# LPC1768.net
KiCad netlist of a schematic drawn in Altium Designer
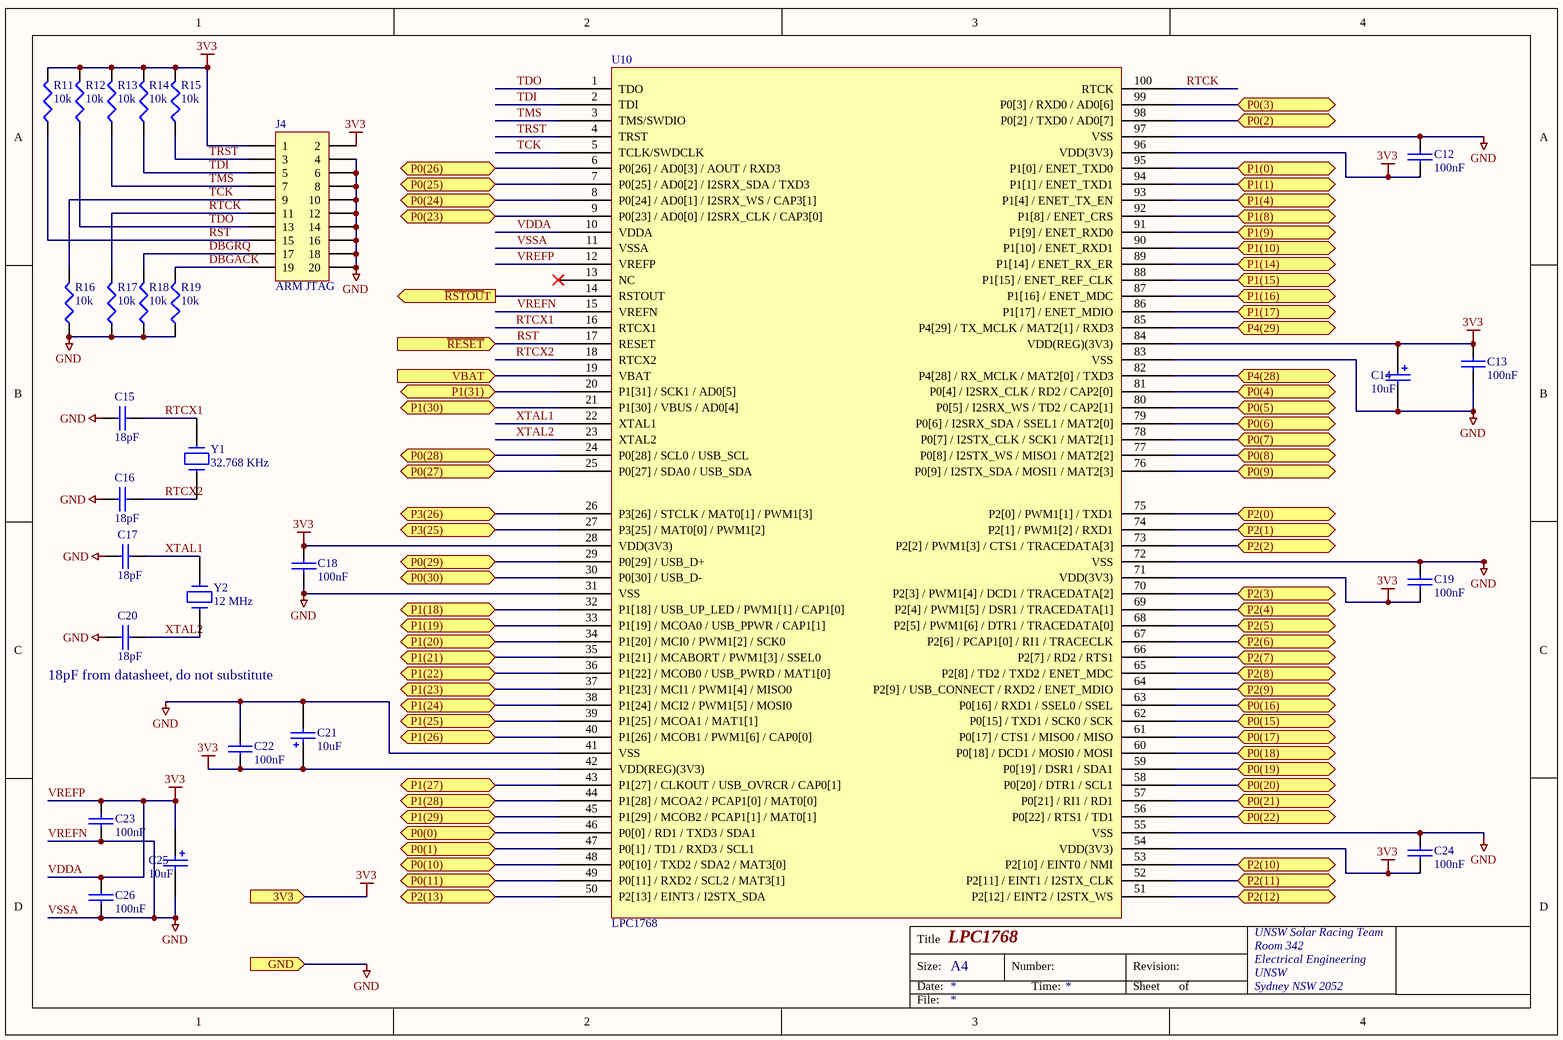
[diagram p0: LPC1768.SchDoc]

(export (version "E")
  (design (tool "Eeschema 10.0.6"))
  (components
    (comp (ref "C12")
      (value "100nF")
      (footprint "0603")
      (description "Capacitor")
      (libsource (lib "RCLDQ") (part "CAP"))
    )
    (comp (ref "C13")
      (value "100nF")
      (footprint "0603")
      (description "Capacitor")
      (libsource (lib "RCLDQ") (part "CAP"))
    )
    (comp (ref "C14")
      (value "10uF")
      (footprint "MCCT-CASEA")
      (description "Polarized Capacitor (Surface Mount)")
      (libsource (lib "RCLDQ") (part "CAP POL3"))
    )
    (comp (ref "C15")
      (value "18pF")
      (footprint "0603")
      (description "Capacitor")
      (libsource (lib "*") (part "CAP"))
    )
    (comp (ref "C16")
      (value "18pF")
      (footprint "0603")
      (description "Capacitor")
      (libsource (lib "*") (part "CAP"))
    )
    (comp (ref "C17")
      (value "18pF")
      (footprint "0603")
      (description "Capacitor")
      (libsource (lib "*") (part "CAP"))
    )
    (comp (ref "C18")
      (value "100nF")
      (footprint "0603")
      (description "Capacitor")
      (libsource (lib "RCLDQ") (part "CAP"))
    )
    (comp (ref "C19")
      (value "100nF")
      (footprint "0603")
      (description "Capacitor")
      (libsource (lib "RCLDQ") (part "CAP"))
    )
    (comp (ref "C20")
      (value "18pF")
      (footprint "0603")
      (description "Capacitor")
      (libsource (lib "*") (part "CAP"))
    )
    (comp (ref "C21")
      (value "10uF")
      (footprint "MCCT-CASEA")
      (description "Polarized Capacitor (Surface Mount)")
      (libsource (lib "RCLDQ") (part "CAP POL3"))
    )
    (comp (ref "C22")
      (value "100nF")
      (footprint "0603")
      (description "Capacitor")
      (libsource (lib "RCLDQ") (part "CAP"))
    )
    (comp (ref "C23")
      (value "100nF")
      (footprint "0603")
      (description "Capacitor")
      (libsource (lib "RCLDQ") (part "CAP"))
    )
    (comp (ref "C24")
      (value "100nF")
      (footprint "0603")
      (description "Capacitor")
      (libsource (lib "RCLDQ") (part "CAP"))
    )
    (comp (ref "C25")
      (value "10uF")
      (footprint "MCCT-CASEA")
      (description "Polarized Capacitor (Surface Mount)")
      (libsource (lib "RCLDQ") (part "CAP POL3"))
    )
    (comp (ref "C26")
      (value "100nF")
      (footprint "0603")
      (description "Capacitor")
      (libsource (lib "RCLDQ") (part "CAP"))
    )
    (comp (ref "J4")
      (value "ARM JTAG")
      (footprint "HDR2X10")
      (description "Header, 10-Pin, Dual row")
      (libsource (lib "Miscellaneous Connectors") (part "Header 10X2"))
    )
    (comp (ref "R11")
      (value "10k")
      (footprint "0603")
      (description "Resistor")
      (libsource (lib "RCLDQ") (part "RES1"))
    )
    (comp (ref "R12")
      (value "10k")
      (footprint "0603")
      (description "Resistor")
      (libsource (lib "RCLDQ") (part "RES1"))
    )
    (comp (ref "R13")
      (value "10k")
      (footprint "0603")
      (description "Resistor")
      (libsource (lib "RCLDQ") (part "RES1"))
    )
    (comp (ref "R14")
      (value "10k")
      (footprint "0603")
      (description "Resistor")
      (libsource (lib "RCLDQ") (part "RES1"))
    )
    (comp (ref "R15")
      (value "10k")
      (footprint "0603")
      (description "Resistor")
      (libsource (lib "RCLDQ") (part "RES1"))
    )
    (comp (ref "R16")
      (value "10k")
      (footprint "0603")
      (description "Resistor")
      (libsource (lib "RCLDQ") (part "RES1"))
    )
    (comp (ref "R17")
      (value "10k")
      (footprint "0603")
      (description "Resistor")
      (libsource (lib "RCLDQ") (part "RES1"))
    )
    (comp (ref "R18")
      (value "10k")
      (footprint "0603")
      (description "Resistor")
      (libsource (lib "RCLDQ") (part "RES1"))
    )
    (comp (ref "R19")
      (value "10k")
      (footprint "0603")
      (description "Resistor")
      (libsource (lib "RCLDQ") (part "RES1"))
    )
    (comp (ref "U10")
      (value "LPC1768")
      (footprint "QFP100")
      (description "NXP Cortex-M3 Microcontroller, 100pin 100MHz")
      (libsource (lib "sion") (part "LPC1768"))
    )
    (comp (ref "Y1")
      (value "32.768 KHz")
      (footprint "WATCHA")
      (description "Crystal")
      (libsource (lib "*") (part "CRYSTAL"))
    )
    (comp (ref "Y2")
      (value "12 MHz")
      (footprint "HC49/4H")
      (description "Crystal")
      (libsource (lib "*") (part "CRYSTAL"))
    )
  )
  (nets
    (net (code "1") (name "/DBGACK") (class "Default")
      (node (ref "J4") (pin "19") (pinfunction "19_19") (pintype "passive"))
      (node (ref "R19") (pin "2") (pinfunction "2_2") (pintype "passive"))
    )
    (net (code "2") (name "/DBGRQ") (class "Default")
      (node (ref "J4") (pin "17") (pinfunction "17_17") (pintype "passive"))
      (node (ref "R18") (pin "2") (pinfunction "2_2") (pintype "passive"))
    )
    (net (code "3") (name "/P0(0)") (class "Default")
      (node (ref "U10") (pin "46") (pinfunction "P0[0]_/_RD1_/_TXD3_/_SDA1_46") (pintype "passive"))
    )
    (net (code "4") (name "/P0(1)") (class "Default")
      (node (ref "U10") (pin "47") (pinfunction "P0[1]_/_TD1_/_RXD3_/_SCL1_47") (pintype "passive"))
    )
    (net (code "5") (name "/P0(2)") (class "Default")
      (node (ref "U10") (pin "98") (pinfunction "P0[2]_/_TXD0_/_AD0[7]_98") (pintype "passive"))
    )
    (net (code "6") (name "/P0(3)") (class "Default")
      (node (ref "U10") (pin "99") (pinfunction "P0[3]_/_RXD0_/_AD0[6]_99") (pintype "passive"))
    )
    (net (code "7") (name "/P0(4)") (class "Default")
      (node (ref "U10") (pin "81") (pinfunction "P0[4]_/_I2SRX_CLK_/_RD2_/_CAP2[0]_81") (pintype "passive"))
    )
    (net (code "8") (name "/P0(5)") (class "Default")
      (node (ref "U10") (pin "80") (pinfunction "P0[5]_/_I2SRX_WS_/_TD2_/_CAP2[1]_80") (pintype "passive"))
    )
    (net (code "9") (name "/P0(6)") (class "Default")
      (node (ref "U10") (pin "79") (pinfunction "P0[6]_/_I2SRX_SDA_/_SSEL1_/_MAT2[0]_79") (pintype "passive"))
    )
    (net (code "10") (name "/P0(7)") (class "Default")
      (node (ref "U10") (pin "78") (pinfunction "P0[7]_/_I2STX_CLK_/_SCK1_/_MAT2[1]_78") (pintype "passive"))
    )
    (net (code "11") (name "/P0(8)") (class "Default")
      (node (ref "U10") (pin "77") (pinfunction "P0[8]_/_I2STX_WS_/_MISO1_/_MAT2[2]_77") (pintype "passive"))
    )
    (net (code "12") (name "/P0(9)") (class "Default")
      (node (ref "U10") (pin "76") (pinfunction "P0[9]_/_I2STX_SDA_/_MOSI1_/_MAT2[3]_76") (pintype "passive"))
    )
    (net (code "13") (name "/P0(10)") (class "Default")
      (node (ref "U10") (pin "48") (pinfunction "P0[10]_/_TXD2_/_SDA2_/_MAT3[0]_48") (pintype "passive"))
    )
    (net (code "14") (name "/P0(11)") (class "Default")
      (node (ref "U10") (pin "49") (pinfunction "P0[11]_/_RXD2_/_SCL2_/_MAT3[1]_49") (pintype "passive"))
    )
    (net (code "15") (name "/P0(15)") (class "Default")
      (node (ref "U10") (pin "62") (pinfunction "P0[15]_/_TXD1_/_SCK0_/_SCK_62") (pintype "passive"))
    )
    (net (code "16") (name "/P0(16)") (class "Default")
      (node (ref "U10") (pin "63") (pinfunction "P0[16]_/_RXD1_/_SSEL0_/_SSEL_63") (pintype "passive"))
    )
    (net (code "17") (name "/P0(17)") (class "Default")
      (node (ref "U10") (pin "61") (pinfunction "P0[17]_/_CTS1_/_MISO0_/_MISO_61") (pintype "passive"))
    )
    (net (code "18") (name "/P0(18)") (class "Default")
      (node (ref "U10") (pin "60") (pinfunction "P0[18]_/_DCD1_/_MOSI0_/_MOSI_60") (pintype "passive"))
    )
    (net (code "19") (name "/P0(19)") (class "Default")
      (node (ref "U10") (pin "59") (pinfunction "P0[19]_/_DSR1_/_SDA1_59") (pintype "passive"))
    )
    (net (code "20") (name "/P0(20)") (class "Default")
      (node (ref "U10") (pin "58") (pinfunction "P0[20]_/_DTR1_/_SCL1_58") (pintype "passive"))
    )
    (net (code "21") (name "/P0(21)") (class "Default")
      (node (ref "U10") (pin "57") (pinfunction "P0[21]_/_RI1_/_RD1_57") (pintype "passive"))
    )
    (net (code "22") (name "/P0(22)") (class "Default")
      (node (ref "U10") (pin "56") (pinfunction "P0[22]_/_RTS1_/_TD1_56") (pintype "passive"))
    )
    (net (code "23") (name "/P0(23)") (class "Default")
      (node (ref "U10") (pin "9") (pinfunction "P0[23]_/_AD0[0]_/_I2SRX_CLK_/_CAP3[0]_9") (pintype "passive"))
    )
    (net (code "24") (name "/P0(24)") (class "Default")
      (node (ref "U10") (pin "8") (pinfunction "P0[24]_/_AD0[1]_/_I2SRX_WS_/_CAP3[1]_8") (pintype "passive"))
    )
    (net (code "25") (name "/P0(25)") (class "Default")
      (node (ref "U10") (pin "7") (pinfunction "P0[25]_/_AD0[2]_/_I2SRX_SDA_/_TXD3_7") (pintype "passive"))
    )
    (net (code "26") (name "/P0(26)") (class "Default")
      (node (ref "U10") (pin "6") (pinfunction "P0[26]_/_AD0[3]_/_AOUT_/_RXD3_6") (pintype "passive"))
    )
    (net (code "27") (name "/P0(27)") (class "Default")
      (node (ref "U10") (pin "25") (pinfunction "P0[27]_/_SDA0_/_USB_SDA_25") (pintype "passive"))
    )
    (net (code "28") (name "/P0(28)") (class "Default")
      (node (ref "U10") (pin "24") (pinfunction "P0[28]_/_SCL0_/_USB_SCL_24") (pintype "passive"))
    )
    (net (code "29") (name "/P0(29)") (class "Default")
      (node (ref "U10") (pin "29") (pinfunction "P0[29]_/_USB_D+_29") (pintype "passive"))
    )
    (net (code "30") (name "/P0(30)") (class "Default")
      (node (ref "U10") (pin "30") (pinfunction "P0[30]_/_USB_D-_30") (pintype "passive"))
    )
    (net (code "31") (name "/P1(0)") (class "Default")
      (node (ref "U10") (pin "95") (pinfunction "P1[0]_/_ENET_TXD0_95") (pintype "passive"))
    )
    (net (code "32") (name "/P1(1)") (class "Default")
      (node (ref "U10") (pin "94") (pinfunction "P1[1]_/_ENET_TXD1_94") (pintype "passive"))
    )
    (net (code "33") (name "/P1(4)") (class "Default")
      (node (ref "U10") (pin "93") (pinfunction "P1[4]_/_ENET_TX_EN_93") (pintype "passive"))
    )
    (net (code "34") (name "/P1(8)") (class "Default")
      (node (ref "U10") (pin "92") (pinfunction "P1[8]_/_ENET_CRS_92") (pintype "passive"))
    )
    (net (code "35") (name "/P1(9)") (class "Default")
      (node (ref "U10") (pin "91") (pinfunction "P1[9]_/_ENET_RXD0_91") (pintype "passive"))
    )
    (net (code "36") (name "/P1(10)") (class "Default")
      (node (ref "U10") (pin "90") (pinfunction "P1[10]_/_ENET_RXD1_90") (pintype "passive"))
    )
    (net (code "37") (name "/P1(14)") (class "Default")
      (node (ref "U10") (pin "89") (pinfunction "P1[14]_/_ENET_RX_ER_89") (pintype "passive"))
    )
    (net (code "38") (name "/P1(15)") (class "Default")
      (node (ref "U10") (pin "88") (pinfunction "P1[15]_/_ENET_REF_CLK_88") (pintype "passive"))
    )
    (net (code "39") (name "/P1(16)") (class "Default")
      (node (ref "U10") (pin "87") (pinfunction "P1[16]_/_ENET_MDC_87") (pintype "passive"))
    )
    (net (code "40") (name "/P1(17)") (class "Default")
      (node (ref "U10") (pin "86") (pinfunction "P1[17]_/_ENET_MDIO_86") (pintype "passive"))
    )
    (net (code "41") (name "/P1(18)") (class "Default")
      (node (ref "U10") (pin "32") (pinfunction "P1[18]_/_USB_UP_LED_/_PWM1[1]_/_CAP1[0]_32") (pintype "passive"))
    )
    (net (code "42") (name "/P1(19)") (class "Default")
      (node (ref "U10") (pin "33") (pinfunction "P1[19]_/_MCOA0_/_USB_PPWR_/_CAP1[1]_33") (pintype "passive"))
    )
    (net (code "43") (name "/P1(20)") (class "Default")
      (node (ref "U10") (pin "34") (pinfunction "P1[20]_/_MCI0_/_PWM1[2]_/_SCK0_34") (pintype "passive"))
    )
    (net (code "44") (name "/P1(21)") (class "Default")
      (node (ref "U10") (pin "35") (pinfunction "P1[21]_/_MCABORT_/_PWM1[3]_/_SSEL0_35") (pintype "passive"))
    )
    (net (code "45") (name "/P1(22)") (class "Default")
      (node (ref "U10") (pin "36") (pinfunction "P1[22]_/_MCOB0_/_USB_PWRD_/_MAT1[0]_36") (pintype "passive"))
    )
    (net (code "46") (name "/P1(23)") (class "Default")
      (node (ref "U10") (pin "37") (pinfunction "P1[23]_/_MCI1_/_PWM1[4]_/_MISO0_37") (pintype "passive"))
    )
    (net (code "47") (name "/P1(24)") (class "Default")
      (node (ref "U10") (pin "38") (pinfunction "P1[24]_/_MCI2_/_PWM1[5]_/_MOSI0_38") (pintype "passive"))
    )
    (net (code "48") (name "/P1(25)") (class "Default")
      (node (ref "U10") (pin "39") (pinfunction "P1[25]_/_MCOA1_/_MAT1[1]_39") (pintype "passive"))
    )
    (net (code "49") (name "/P1(26)") (class "Default")
      (node (ref "U10") (pin "40") (pinfunction "P1[26]_/_MCOB1_/_PWM1[6]_/_CAP0[0]_40") (pintype "passive"))
    )
    (net (code "50") (name "/P1(27)") (class "Default")
      (node (ref "U10") (pin "43") (pinfunction "P1[27]_/_CLKOUT_/_USB_OVRCR_/_CAP0[1]_43") (pintype "passive"))
    )
    (net (code "51") (name "/P1(28)") (class "Default")
      (node (ref "U10") (pin "44") (pinfunction "P1[28]_/_MCOA2_/_PCAP1[0]_/_MAT0[0]_44") (pintype "passive"))
    )
    (net (code "52") (name "/P1(29)") (class "Default")
      (node (ref "U10") (pin "45") (pinfunction "P1[29]_/_MCOB2_/_PCAP1[1]_/_MAT0[1]_45") (pintype "passive"))
    )
    (net (code "53") (name "/P1(30)") (class "Default")
      (node (ref "U10") (pin "21") (pinfunction "P1[30]_/_VBUS_/_AD0[4]_21") (pintype "passive"))
    )
    (net (code "54") (name "/P1(31)") (class "Default")
      (node (ref "U10") (pin "20") (pinfunction "P1[31]_/_SCK1_/_AD0[5]_20") (pintype "passive"))
    )
    (net (code "55") (name "/P2(0)") (class "Default")
      (node (ref "U10") (pin "75") (pinfunction "P2[0]_/_PWM1[1]_/_TXD1_75") (pintype "passive"))
    )
    (net (code "56") (name "/P2(1)") (class "Default")
      (node (ref "U10") (pin "74") (pinfunction "P2[1]_/_PWM1[2]_/_RXD1_74") (pintype "passive"))
    )
    (net (code "57") (name "/P2(2)") (class "Default")
      (node (ref "U10") (pin "73") (pinfunction "P2[2]_/_PWM1[3]_/_CTS1_/_TRACEDATA[3]_73") (pintype "passive"))
    )
    (net (code "58") (name "/P2(3)") (class "Default")
      (node (ref "U10") (pin "70") (pinfunction "P2[3]_/_PWM1[4]_/_DCD1_/_TRACEDATA[2]_70") (pintype "passive"))
    )
    (net (code "59") (name "/P2(4)") (class "Default")
      (node (ref "U10") (pin "69") (pinfunction "P2[4]_/_PWM1[5]_/_DSR1_/_TRACEDATA[1]_69") (pintype "passive"))
    )
    (net (code "60") (name "/P2(5)") (class "Default")
      (node (ref "U10") (pin "68") (pinfunction "P2[5]_/_PWM1[6]_/_DTR1_/_TRACEDATA[0]_68") (pintype "passive"))
    )
    (net (code "61") (name "/P2(6)") (class "Default")
      (node (ref "U10") (pin "67") (pinfunction "P2[6]_/_PCAP1[0]_/_RI1_/_TRACECLK_67") (pintype "passive"))
    )
    (net (code "62") (name "/P2(7)") (class "Default")
      (node (ref "U10") (pin "66") (pinfunction "P2[7]_/_RD2_/_RTS1_66") (pintype "passive"))
    )
    (net (code "63") (name "/P2(8)") (class "Default")
      (node (ref "U10") (pin "65") (pinfunction "P2[8]_/_TD2_/_TXD2_/_ENET_MDC_65") (pintype "passive"))
    )
    (net (code "64") (name "/P2(9)") (class "Default")
      (node (ref "U10") (pin "64") (pinfunction "P2[9]_/_USB_CONNECT_/_RXD2_/_ENET_MDIO_64") (pintype "passive"))
    )
    (net (code "65") (name "/P2(10)") (class "Default")
      (node (ref "U10") (pin "53") (pinfunction "P2[10]_/_EINT0_/_NMI_53") (pintype "passive"))
    )
    (net (code "66") (name "/P2(11)") (class "Default")
      (node (ref "U10") (pin "52") (pinfunction "P2[11]_/_EINT1_/_I2STX_CLK_52") (pintype "passive"))
    )
    (net (code "67") (name "/P2(12)") (class "Default")
      (node (ref "U10") (pin "51") (pinfunction "P2[12]_/_EINT2_/_I2STX_WS_51") (pintype "passive"))
    )
    (net (code "68") (name "/P2(13)") (class "Default")
      (node (ref "U10") (pin "50") (pinfunction "P2[13]_/_EINT3_/_I2STX_SDA_50") (pintype "passive"))
    )
    (net (code "69") (name "/P3(25)") (class "Default")
      (node (ref "U10") (pin "27") (pinfunction "P3[25]_/_MAT0[0]_/_PWM1[2]_27") (pintype "passive"))
    )
    (net (code "70") (name "/P3(26)") (class "Default")
      (node (ref "U10") (pin "26") (pinfunction "P3[26]_/_STCLK_/_MAT0[1]_/_PWM1[3]_26") (pintype "passive"))
    )
    (net (code "71") (name "/P4(28)") (class "Default")
      (node (ref "U10") (pin "82") (pinfunction "P4[28]_/_RX_MCLK_/_MAT2[0]_/_TXD3_82") (pintype "passive"))
    )
    (net (code "72") (name "/P4(29)") (class "Default")
      (node (ref "U10") (pin "85") (pinfunction "P4[29]_/_TX_MCLK_/_MAT2[1]_/_RXD3_85") (pintype "passive"))
    )
    (net (code "73") (name "/RST") (class "Default")
      (node (ref "J4") (pin "15") (pinfunction "15_15") (pintype "passive"))
      (node (ref "R11") (pin "1") (pinfunction "1_1") (pintype "passive"))
      (node (ref "U10") (pin "17") (pinfunction "RESET_17") (pintype "passive"))
    )
    (net (code "74") (name "/RTCK") (class "Default")
      (node (ref "J4") (pin "11") (pinfunction "11_11") (pintype "passive"))
      (node (ref "R17") (pin "2") (pinfunction "2_2") (pintype "passive"))
      (node (ref "U10") (pin "100") (pinfunction "RTCK_100") (pintype "passive"))
    )
    (net (code "75") (name "/RTCX1") (class "Default")
      (node (ref "C15") (pin "1") (pinfunction "1_1") (pintype "passive"))
      (node (ref "U10") (pin "16") (pinfunction "RTCX1_16") (pintype "passive"))
      (node (ref "Y1") (pin "2") (pinfunction "2_2") (pintype "passive"))
    )
    (net (code "76") (name "/RTCX2") (class "Default")
      (node (ref "C16") (pin "1") (pinfunction "1_1") (pintype "passive"))
      (node (ref "U10") (pin "18") (pinfunction "RTCX2_18") (pintype "passive"))
      (node (ref "Y1") (pin "1") (pinfunction "1_1") (pintype "passive"))
    )
    (net (code "77") (name "/TCK") (class "Default")
      (node (ref "J4") (pin "9") (pinfunction "9_9") (pintype "passive"))
      (node (ref "R16") (pin "2") (pinfunction "2_2") (pintype "passive"))
      (node (ref "U10") (pin "5") (pinfunction "TCLK/SWDCLK_5") (pintype "passive"))
    )
    (net (code "78") (name "/TDI") (class "Default")
      (node (ref "J4") (pin "5") (pinfunction "5_5") (pintype "passive"))
      (node (ref "R14") (pin "1") (pinfunction "1_1") (pintype "passive"))
      (node (ref "U10") (pin "2") (pinfunction "TDI_2") (pintype "passive"))
    )
    (net (code "79") (name "/TDO") (class "Default")
      (node (ref "J4") (pin "13") (pinfunction "13_13") (pintype "passive"))
      (node (ref "R12") (pin "1") (pinfunction "1_1") (pintype "passive"))
      (node (ref "U10") (pin "1") (pinfunction "TDO_1") (pintype "passive"))
    )
    (net (code "80") (name "/TMS") (class "Default")
      (node (ref "J4") (pin "7") (pinfunction "7_7") (pintype "passive"))
      (node (ref "R13") (pin "1") (pinfunction "1_1") (pintype "passive"))
      (node (ref "U10") (pin "3") (pinfunction "TMS/SWDIO_3") (pintype "passive"))
    )
    (net (code "81") (name "/TRST") (class "Default")
      (node (ref "J4") (pin "3") (pinfunction "3_3") (pintype "passive"))
      (node (ref "R15") (pin "1") (pinfunction "1_1") (pintype "passive"))
      (node (ref "U10") (pin "4") (pinfunction "TRST_4") (pintype "passive"))
    )
    (net (code "82") (name "/VBAT") (class "Default")
      (node (ref "U10") (pin "19") (pinfunction "VBAT_19") (pintype "passive"))
    )
    (net (code "83") (name "/XTAL1") (class "Default")
      (node (ref "C17") (pin "1") (pinfunction "1_1") (pintype "passive"))
      (node (ref "U10") (pin "22") (pinfunction "XTAL1_22") (pintype "passive"))
      (node (ref "Y2") (pin "1") (pinfunction "1_1") (pintype "passive"))
    )
    (net (code "84") (name "/XTAL2") (class "Default")
      (node (ref "C20") (pin "1") (pinfunction "1_1") (pintype "passive"))
      (node (ref "U10") (pin "23") (pinfunction "XTAL2_23") (pintype "passive"))
      (node (ref "Y2") (pin "2") (pinfunction "2_2") (pintype "passive"))
    )
    (net (code "85") (name "/~{RSTOU}T") (class "Default")
      (node (ref "U10") (pin "14") (pinfunction "RSTOUT_14") (pintype "passive"))
    )
    (net (code "86") (name "3V3") (class "Default")
      (node (ref "C12") (pin "2") (pinfunction "2_2") (pintype "passive"))
      (node (ref "C13") (pin "1") (pinfunction "1_1") (pintype "passive"))
      (node (ref "C14") (pin "1") (pinfunction "1_1") (pintype "passive"))
      (node (ref "C18") (pin "1") (pinfunction "1_1") (pintype "passive"))
      (node (ref "C19") (pin "2") (pinfunction "2_2") (pintype "passive"))
      (node (ref "C21") (pin "1") (pinfunction "1_1") (pintype "passive"))
      (node (ref "C22") (pin "2") (pinfunction "2_2") (pintype "passive"))
      (node (ref "C23") (pin "1") (pinfunction "1_1") (pintype "passive"))
      (node (ref "C24") (pin "2") (pinfunction "2_2") (pintype "passive"))
      (node (ref "C25") (pin "1") (pinfunction "1_1") (pintype "passive"))
      (node (ref "C26") (pin "1") (pinfunction "1_1") (pintype "passive"))
      (node (ref "J4") (pin "1") (pinfunction "1_1") (pintype "passive"))
      (node (ref "J4") (pin "2") (pinfunction "2_2") (pintype "passive"))
      (node (ref "R11") (pin "2") (pinfunction "2_2") (pintype "passive"))
      (node (ref "R12") (pin "2") (pinfunction "2_2") (pintype "passive"))
      (node (ref "R13") (pin "2") (pinfunction "2_2") (pintype "passive"))
      (node (ref "R14") (pin "2") (pinfunction "2_2") (pintype "passive"))
      (node (ref "R15") (pin "2") (pinfunction "2_2") (pintype "passive"))
      (node (ref "U10") (pin "10") (pinfunction "VDDA_10") (pintype "passive"))
      (node (ref "U10") (pin "12") (pinfunction "VREFP_12") (pintype "passive"))
      (node (ref "U10") (pin "28") (pinfunction "VDD(3V3)_28") (pintype "passive"))
      (node (ref "U10") (pin "42") (pinfunction "VDD(REG)(3V3)_42") (pintype "passive"))
      (node (ref "U10") (pin "54") (pinfunction "VDD(3V3)_54") (pintype "passive"))
      (node (ref "U10") (pin "71") (pinfunction "VDD(3V3)_71") (pintype "passive"))
      (node (ref "U10") (pin "84") (pinfunction "VDD(REG)(3V3)_84") (pintype "passive"))
      (node (ref "U10") (pin "96") (pinfunction "VDD(3V3)_96") (pintype "passive"))
    )
    (net (code "87") (name "GND") (class "Default")
      (node (ref "C12") (pin "1") (pinfunction "1_1") (pintype "passive"))
      (node (ref "C13") (pin "2") (pinfunction "2_2") (pintype "passive"))
      (node (ref "C14") (pin "2") (pinfunction "2_2") (pintype "passive"))
      (node (ref "C15") (pin "2") (pinfunction "2_2") (pintype "passive"))
      (node (ref "C16") (pin "2") (pinfunction "2_2") (pintype "passive"))
      (node (ref "C17") (pin "2") (pinfunction "2_2") (pintype "passive"))
      (node (ref "C18") (pin "2") (pinfunction "2_2") (pintype "passive"))
      (node (ref "C19") (pin "1") (pinfunction "1_1") (pintype "passive"))
      (node (ref "C20") (pin "2") (pinfunction "2_2") (pintype "passive"))
      (node (ref "C21") (pin "2") (pinfunction "2_2") (pintype "passive"))
      (node (ref "C22") (pin "1") (pinfunction "1_1") (pintype "passive"))
      (node (ref "C23") (pin "2") (pinfunction "2_2") (pintype "passive"))
      (node (ref "C24") (pin "1") (pinfunction "1_1") (pintype "passive"))
      (node (ref "C25") (pin "2") (pinfunction "2_2") (pintype "passive"))
      (node (ref "C26") (pin "2") (pinfunction "2_2") (pintype "passive"))
      (node (ref "J4") (pin "10") (pinfunction "10_10") (pintype "passive"))
      (node (ref "J4") (pin "12") (pinfunction "12_12") (pintype "passive"))
      (node (ref "J4") (pin "14") (pinfunction "14_14") (pintype "passive"))
      (node (ref "J4") (pin "16") (pinfunction "16_16") (pintype "passive"))
      (node (ref "J4") (pin "18") (pinfunction "18_18") (pintype "passive"))
      (node (ref "J4") (pin "20") (pinfunction "20_20") (pintype "passive"))
      (node (ref "J4") (pin "4") (pinfunction "4_4") (pintype "passive"))
      (node (ref "J4") (pin "6") (pinfunction "6_6") (pintype "passive"))
      (node (ref "J4") (pin "8") (pinfunction "8_8") (pintype "passive"))
      (node (ref "R16") (pin "1") (pinfunction "1_1") (pintype "passive"))
      (node (ref "R17") (pin "1") (pinfunction "1_1") (pintype "passive"))
      (node (ref "R18") (pin "1") (pinfunction "1_1") (pintype "passive"))
      (node (ref "R19") (pin "1") (pinfunction "1_1") (pintype "passive"))
      (node (ref "U10") (pin "11") (pinfunction "VSSA_11") (pintype "passive"))
      (node (ref "U10") (pin "15") (pinfunction "VREFN_15") (pintype "passive"))
      (node (ref "U10") (pin "31") (pinfunction "VSS_31") (pintype "passive"))
      (node (ref "U10") (pin "41") (pinfunction "VSS_41") (pintype "passive"))
      (node (ref "U10") (pin "55") (pinfunction "VSS_55") (pintype "passive"))
      (node (ref "U10") (pin "72") (pinfunction "VSS_72") (pintype "passive"))
      (node (ref "U10") (pin "83") (pinfunction "VSS_83") (pintype "passive"))
      (node (ref "U10") (pin "97") (pinfunction "VSS_97") (pintype "passive"))
    )
    (net (code "88") (name "unconnected-(U10-NC-Pad13)") (class "Default")
      (node (ref "U10") (pin "13") (pinfunction "NC_13") (pintype "passive+no_connect"))
    )
  )
)
